# sch_acdc_standart.net
KiCad netlist of a schematic drawn in Altium Designer
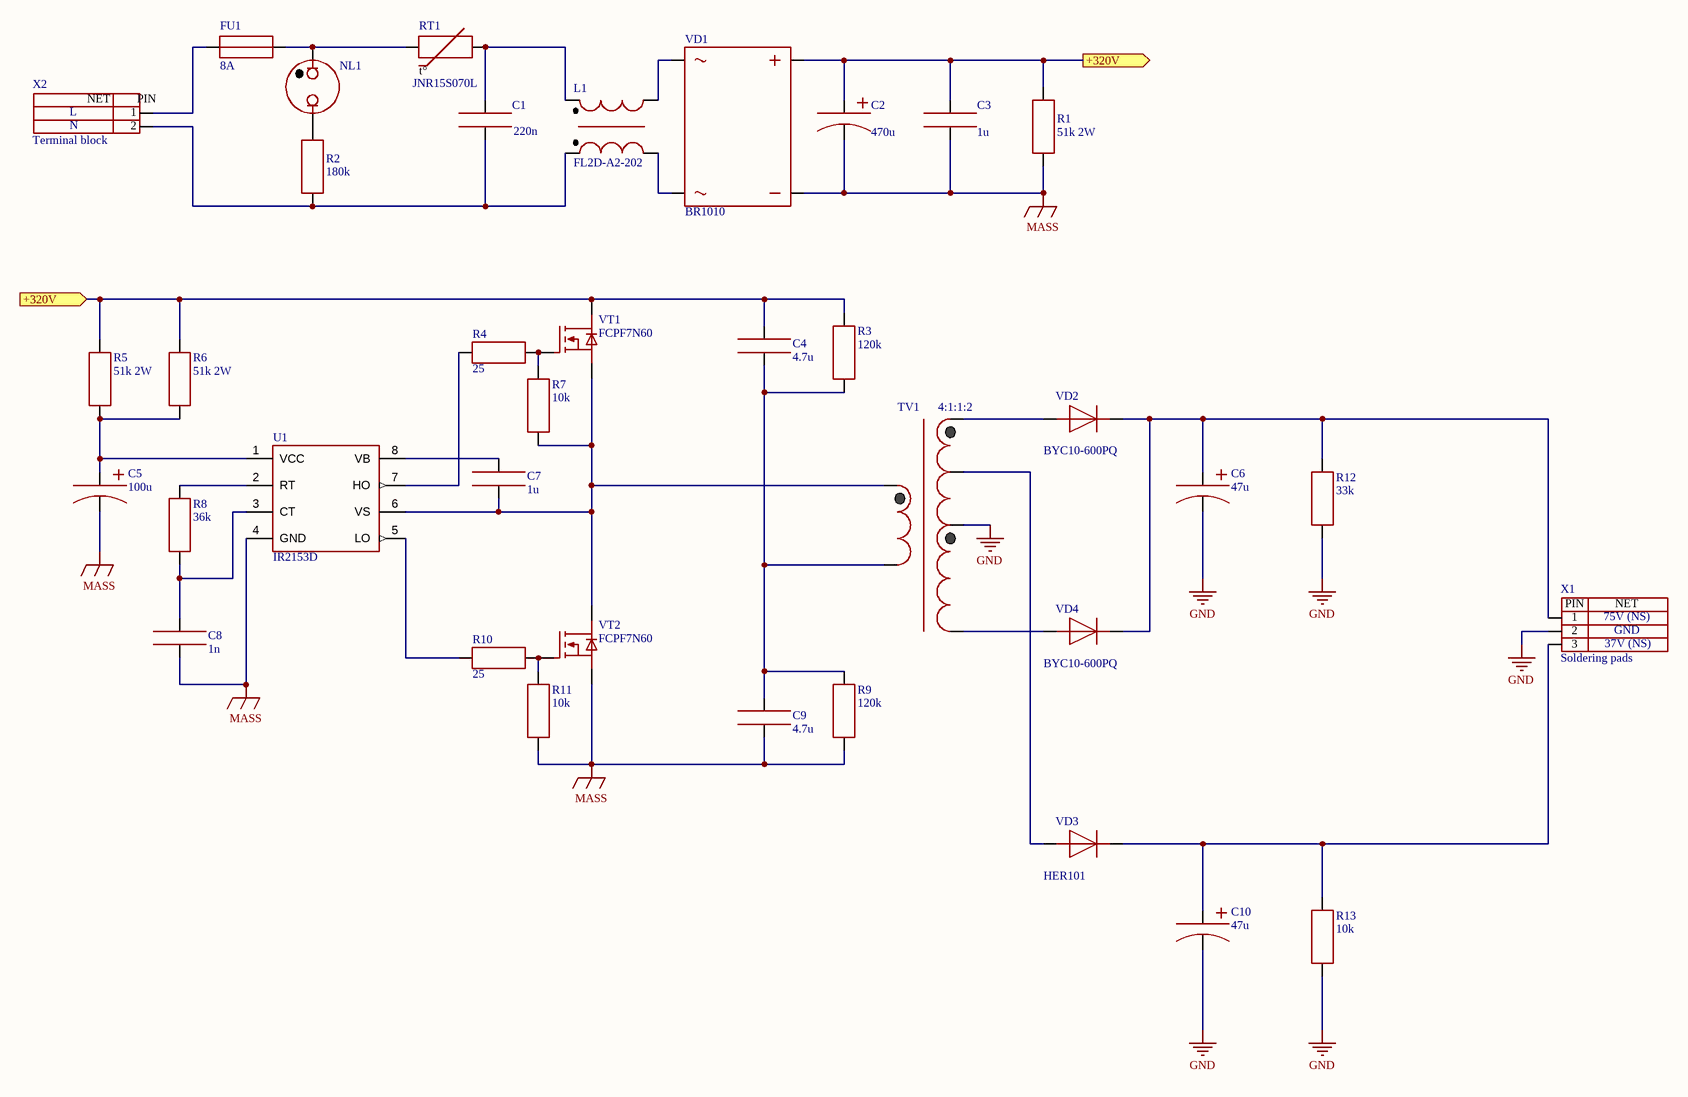
[diagram p0: sch(acdc, standart).SchDoc]

(export (version "E")
  (design (tool "Eeschema 10.0.6"))
  (components
    (comp (ref "C1")
      (value "220n")
      (footprint "Конд_эмп P 15ММ")
      (libsource (lib "LeeSch") (part "Capacitor"))
    )
    (comp (ref "C2")
      (value "470u")
      (footprint "кондер ELEC D35.00mm S10.00mm H40.00mm")
      (libsource (lib "LeeSch") (part "Capacitor (Electrolytic)"))
    )
    (comp (ref "C3")
      (value "1u")
      (footprint "Конд_плен - P 20мм")
      (libsource (lib "LeeSch") (part "Capacitor"))
    )
    (comp (ref "C4")
      (value "4.7u")
      (footprint "конд металопленочный P 31мм")
      (description "К73-17")
      (libsource (lib "LeeSch") (part "Capacitor"))
    )
    (comp (ref "C5")
      (value "100u")
      (footprint "конд ELEC D6.30mm S2.50mm H11.00mm")
      (description "K50-35 25V")
      (libsource (lib "LeeSch") (part "Capacitor (Electrolytic)"))
    )
    (comp (ref "C6")
      (value "47u")
      (footprint "конд ELEC D5.00mm S2.00mm H11.00mm")
      (description "К50-35 100V")
      (libsource (lib "LeeSch") (part "Capacitor (Electrolytic)"))
    )
    (comp (ref "C7")
      (value "1u")
      (footprint "конд. кер. мн. слойные")
      (libsource (lib "LeeSch") (part "Capacitor"))
    )
    (comp (ref "C8")
      (value "1n")
      (footprint "конд. кер. мн. слойные")
      (libsource (lib "LeeSch") (part "Capacitor"))
    )
    (comp (ref "C9")
      (value "4.7u")
      (footprint "конд металопленочный P 31мм")
      (description "К73-17")
      (libsource (lib "LeeSch") (part "Capacitor"))
    )
    (comp (ref "C10")
      (value "47u")
      (footprint "конд ELEC D6.30mm S2.50mm H11.00mm")
      (description "К50-35 50V")
      (libsource (lib "LeeSch") (part "Capacitor (Electrolytic)"))
    )
    (comp (ref "FU1") (value "8A") (footprint "предохранитель 20х5") (libsource (lib "LeeSch") (part "Fuse")))
    (comp (ref "L1")
      (value "FL2D-A2-202")
      (footprint "синфазный дросель FL2D-A2-202")
      (description "2x2mH, 12A, 2x145mOhm")
      (libsource (lib "LeeSch") (part "Common Choke"))
    )
    (comp (ref "NL1")
      (value "Lamp (Neon)")
      (footprint "2 PIN")
      (libsource (lib "LeeSch") (part "Lamp (Neon)"))
    )
    (comp (ref "R1")
      (value "51k 2W")
      (footprint "Res 2w")
      (description "2W")
      (libsource (lib "") (part "Resistor_1"))
    )
    (comp (ref "R2") (value "180k") (footprint "R1206") (libsource (lib "") (part "Resistor_1")))
    (comp (ref "R3") (value "120k") (footprint "R1206") (libsource (lib "") (part "Resistor_2")))
    (comp (ref "R4") (value "25") (footprint "R1206") (libsource (lib "LeeSch") (part "Resistor")))
    (comp (ref "R5") (value "51k 2W") (footprint "Res 2w") (libsource (lib "") (part "Resistor_1")))
    (comp (ref "R6") (value "51k 2W") (footprint "Res 2w") (libsource (lib "") (part "Resistor_1")))
    (comp (ref "R7") (value "10k") (footprint "R1206") (libsource (lib "") (part "Resistor_1")))
    (comp (ref "R8") (value "36k") (footprint "R1206") (libsource (lib "") (part "Resistor_1")))
    (comp (ref "R9") (value "120k") (footprint "R1206") (libsource (lib "") (part "Resistor_2")))
    (comp (ref "R10") (value "25") (footprint "R1206") (libsource (lib "LeeSch") (part "Resistor")))
    (comp (ref "R11") (value "10k") (footprint "R1206") (libsource (lib "") (part "Resistor_1")))
    (comp (ref "R12") (value "33k") (footprint "R1206") (libsource (lib "") (part "Resistor_1")))
    (comp (ref "R13") (value "10k") (footprint "R1206") (libsource (lib "") (part "Resistor_1")))
    (comp (ref "RT1")
      (value "JNR15S070L")
      (footprint "NTC 15мм (посадочное8мм)")
      (libsource (lib "LeeSch") (part "Thermistor"))
    )
    (comp (ref "TV1")
      (value "4:1:1:2")
      (footprint "Imp trans (2 wind, 2 sold)")
      (libsource (lib "LeeSch") (part "Transformer (2 Windings, 2 Soldering)"))
    )
    (comp (ref "U1")
      (value "IR2153D")
      (footprint "DIP 8")
      (libsource (lib "LeeSch") (part "IC_Driver_IR2153"))
    )
    (comp (ref "VD1")
      (value "BR1010")
      (footprint "BR_10(диодный мост)")
      (libsource (lib "LeeSch") (part "Diode Bridge (1 Phase)"))
    )
    (comp (ref "VD2")
      (value "BYC10-600PQ")
      (footprint "TO-220-top(2 PIN DIODE)")
      (libsource (lib "LeeSch") (part "Diode"))
    )
    (comp (ref "VD3") (value "HER101") (footprint "DO-41") (libsource (lib "LeeSch") (part "Diode")))
    (comp (ref "VD4")
      (value "BYC10-600PQ")
      (footprint "TO-220-top(2 PIN DIODE)")
      (libsource (lib "LeeSch") (part "Diode"))
    )
    (comp (ref "VT1")
      (value "FCPF7N60")
      (footprint "TO-220-top")
      (libsource (lib "LeeSch") (part "Transistor (MOSFET, N, EMode)"))
    )
    (comp (ref "VT2")
      (value "FCPF7N60")
      (footprint "TO-220-top")
      (libsource (lib "LeeSch") (part "Transistor (MOSFET, N, EMode)"))
    )
    (comp (ref "X1")
      (value "Soldering pads")
      (footprint "place 3")
      (libsource (lib "LeeSch") (part "Terminal block (3-pin)"))
    )
    (comp (ref "X2")
      (value "Terminal block")
      (footprint "5мм")
      (libsource (lib "LeeSch") (part "Terminal block (2-pin)"))
    )
  )
  (nets
    (net (code "1") (name "/+320V") (class "Default")
      (node (ref "C2") (pin "1") (pinfunction "1_1") (pintype "passive"))
      (node (ref "C3") (pin "2") (pinfunction "2_2") (pintype "passive"))
      (node (ref "C4") (pin "1") (pinfunction "1_1") (pintype "passive"))
      (node (ref "R1") (pin "2") (pinfunction "2_2") (pintype "passive"))
      (node (ref "R3") (pin "1") (pinfunction "1_1") (pintype "passive"))
      (node (ref "R5") (pin "2") (pinfunction "2_2") (pintype "passive"))
      (node (ref "R6") (pin "2") (pinfunction "2_2") (pintype "passive"))
      (node (ref "VD1") (pin "4") (pinfunction "+_4") (pintype "passive"))
      (node (ref "VT1") (pin "2") (pinfunction "Drain_2") (pintype "passive"))
    )
    (net (code "2") (name "GND") (class "Default")
      (node (ref "C10") (pin "2") (pinfunction "2_2") (pintype "passive"))
      (node (ref "C6") (pin "2") (pinfunction "2_2") (pintype "passive"))
      (node (ref "R12") (pin "1") (pinfunction "1_1") (pintype "passive"))
      (node (ref "R13") (pin "1") (pinfunction "1_1") (pintype "passive"))
      (node (ref "TV1") (pin "5") (pinfunction "5_5") (pintype "passive"))
      (node (ref "X1") (pin "2") (pinfunction "NET2_2") (pintype "passive"))
    )
    (net (code "3") (name "MASS") (class "Default")
      (node (ref "C2") (pin "2") (pinfunction "2_2") (pintype "passive"))
      (node (ref "C3") (pin "1") (pinfunction "1_1") (pintype "passive"))
      (node (ref "C5") (pin "2") (pinfunction "2_2") (pintype "passive"))
      (node (ref "C8") (pin "1") (pinfunction "1_1") (pintype "passive"))
      (node (ref "C9") (pin "2") (pinfunction "2_2") (pintype "passive"))
      (node (ref "R1") (pin "1") (pinfunction "1_1") (pintype "passive"))
      (node (ref "R11") (pin "1") (pinfunction "1_1") (pintype "passive"))
      (node (ref "R9") (pin "2") (pinfunction "2_2") (pintype "passive"))
      (node (ref "U1") (pin "4") (pinfunction "GND_4") (pintype "power_in"))
      (node (ref "VD1") (pin "3") (pinfunction "-_3") (pintype "passive"))
      (node (ref "VT2") (pin "3") (pinfunction "Source_3") (pintype "passive"))
    )
    (net (code "4") (name "Net-(C1-Pad2)") (class "Default")
      (node (ref "C1") (pin "2") (pinfunction "2_2") (pintype "passive"))
      (node (ref "L1") (pin "1") (pinfunction "1_1") (pintype "passive"))
      (node (ref "RT1") (pin "2") (pinfunction "2_2") (pintype "passive"))
    )
    (net (code "5") (name "Net-(C4-Pad2)") (class "Default")
      (node (ref "C4") (pin "2") (pinfunction "2_2") (pintype "passive"))
      (node (ref "C9") (pin "1") (pinfunction "1_1") (pintype "passive"))
      (node (ref "R3") (pin "2") (pinfunction "2_2") (pintype "passive"))
      (node (ref "R9") (pin "1") (pinfunction "1_1") (pintype "passive"))
      (node (ref "TV1") (pin "2") (pinfunction "2_2") (pintype "passive"))
    )
    (net (code "6") (name "Net-(FU1-Pad2)") (class "Default")
      (node (ref "FU1") (pin "2") (pinfunction "2_2") (pintype "passive"))
      (node (ref "NL1") (pin "2") (pinfunction "2_2") (pintype "passive"))
      (node (ref "RT1") (pin "1") (pinfunction "1_1") (pintype "passive"))
    )
    (net (code "7") (name "Net-(L1-Pad3)") (class "Default")
      (node (ref "L1") (pin "3") (pinfunction "3_3") (pintype "passive"))
      (node (ref "VD1") (pin "2") (pinfunction "~_2") (pintype "passive"))
    )
    (net (code "8") (name "Net-(L1-Pad4)") (class "Default")
      (node (ref "L1") (pin "4") (pinfunction "4_4") (pintype "passive"))
      (node (ref "VD1") (pin "1") (pinfunction "~_1") (pintype "passive"))
    )
    (net (code "9") (name "Net-(NL1-Pad1)") (class "Default")
      (node (ref "NL1") (pin "1") (pinfunction "1_1") (pintype "passive"))
      (node (ref "R2") (pin "2") (pinfunction "2_2") (pintype "passive"))
    )
    (net (code "10") (name "Net-(U1-CT)") (class "Default")
      (node (ref "C8") (pin "2") (pinfunction "2_2") (pintype "passive"))
      (node (ref "R8") (pin "1") (pinfunction "1_1") (pintype "passive"))
      (node (ref "U1") (pin "3") (pinfunction "CT_3") (pintype "passive"))
    )
    (net (code "11") (name "Net-(U1-HO)") (class "Default")
      (node (ref "R4") (pin "1") (pinfunction "1_1") (pintype "passive"))
      (node (ref "U1") (pin "7") (pinfunction "HO_7") (pintype "output"))
    )
    (net (code "12") (name "Net-(U1-LO)") (class "Default")
      (node (ref "R10") (pin "1") (pinfunction "1_1") (pintype "passive"))
      (node (ref "U1") (pin "5") (pinfunction "LO_5") (pintype "output"))
    )
    (net (code "13") (name "Net-(U1-RT)") (class "Default")
      (node (ref "R8") (pin "2") (pinfunction "2_2") (pintype "passive"))
      (node (ref "U1") (pin "2") (pinfunction "RT_2") (pintype "passive"))
    )
    (net (code "14") (name "Net-(U1-VB)") (class "Default")
      (node (ref "C7") (pin "2") (pinfunction "2_2") (pintype "passive"))
      (node (ref "U1") (pin "8") (pinfunction "VB_8") (pintype "passive"))
    )
    (net (code "15") (name "Net-(U1-VCC)") (class "Default")
      (node (ref "C5") (pin "1") (pinfunction "1_1") (pintype "passive"))
      (node (ref "R5") (pin "1") (pinfunction "1_1") (pintype "passive"))
      (node (ref "R6") (pin "1") (pinfunction "1_1") (pintype "passive"))
      (node (ref "U1") (pin "1") (pinfunction "VCC_1") (pintype "power_in"))
    )
    (net (code "16") (name "Net-(U1-VS)") (class "Default")
      (node (ref "C7") (pin "1") (pinfunction "1_1") (pintype "passive"))
      (node (ref "R7") (pin "1") (pinfunction "1_1") (pintype "passive"))
      (node (ref "TV1") (pin "1") (pinfunction "1_1") (pintype "passive"))
      (node (ref "U1") (pin "6") (pinfunction "VS_6") (pintype "passive"))
      (node (ref "VT1") (pin "3") (pinfunction "Source_3") (pintype "passive"))
      (node (ref "VT2") (pin "2") (pinfunction "Drain_2") (pintype "passive"))
    )
    (net (code "17") (name "Net-(VD2-Anode)") (class "Default")
      (node (ref "TV1") (pin "3") (pinfunction "3_3") (pintype "passive"))
      (node (ref "VD2") (pin "1") (pinfunction "Anode_1") (pintype "passive"))
    )
    (net (code "18") (name "Net-(VD2-Cathode)") (class "Default")
      (node (ref "C6") (pin "1") (pinfunction "1_1") (pintype "passive"))
      (node (ref "R12") (pin "2") (pinfunction "2_2") (pintype "passive"))
      (node (ref "VD2") (pin "2") (pinfunction "Cathode_2") (pintype "passive"))
      (node (ref "VD4") (pin "2") (pinfunction "Cathode_2") (pintype "passive"))
      (node (ref "X1") (pin "1") (pinfunction "NET1_1") (pintype "passive"))
    )
    (net (code "19") (name "Net-(VD3-Anode)") (class "Default")
      (node (ref "TV1") (pin "4") (pinfunction "4_4") (pintype "passive"))
      (node (ref "VD3") (pin "1") (pinfunction "Anode_1") (pintype "passive"))
    )
    (net (code "20") (name "Net-(VD3-Cathode)") (class "Default")
      (node (ref "C10") (pin "1") (pinfunction "1_1") (pintype "passive"))
      (node (ref "R13") (pin "2") (pinfunction "2_2") (pintype "passive"))
      (node (ref "VD3") (pin "2") (pinfunction "Cathode_2") (pintype "passive"))
      (node (ref "X1") (pin "3") (pinfunction "NET3_3") (pintype "passive"))
    )
    (net (code "21") (name "Net-(VD4-Anode)") (class "Default")
      (node (ref "TV1") (pin "6") (pinfunction "6_6") (pintype "passive"))
      (node (ref "VD4") (pin "1") (pinfunction "Anode_1") (pintype "passive"))
    )
    (net (code "22") (name "Net-(VT1-Gate)") (class "Default")
      (node (ref "R4") (pin "2") (pinfunction "2_2") (pintype "passive"))
      (node (ref "R7") (pin "2") (pinfunction "2_2") (pintype "passive"))
      (node (ref "VT1") (pin "1") (pinfunction "Gate_1") (pintype "passive"))
    )
    (net (code "23") (name "Net-(VT2-Gate)") (class "Default")
      (node (ref "R10") (pin "2") (pinfunction "2_2") (pintype "passive"))
      (node (ref "R11") (pin "2") (pinfunction "2_2") (pintype "passive"))
      (node (ref "VT2") (pin "1") (pinfunction "Gate_1") (pintype "passive"))
    )
    (net (code "24") (name "Net-(X2-NET1)") (class "Default")
      (node (ref "FU1") (pin "1") (pinfunction "1_1") (pintype "passive"))
      (node (ref "X2") (pin "1") (pinfunction "NET1_1") (pintype "passive"))
    )
    (net (code "25") (name "Net-(X2-NET2)") (class "Default")
      (node (ref "C1") (pin "1") (pinfunction "1_1") (pintype "passive"))
      (node (ref "L1") (pin "2") (pinfunction "2_2") (pintype "passive"))
      (node (ref "R2") (pin "1") (pinfunction "1_1") (pintype "passive"))
      (node (ref "X2") (pin "2") (pinfunction "NET2_2") (pintype "passive"))
    )
  )
)
